# iPlayer.net
KiCad netlist of a schematic drawn in EasyEDA Pro
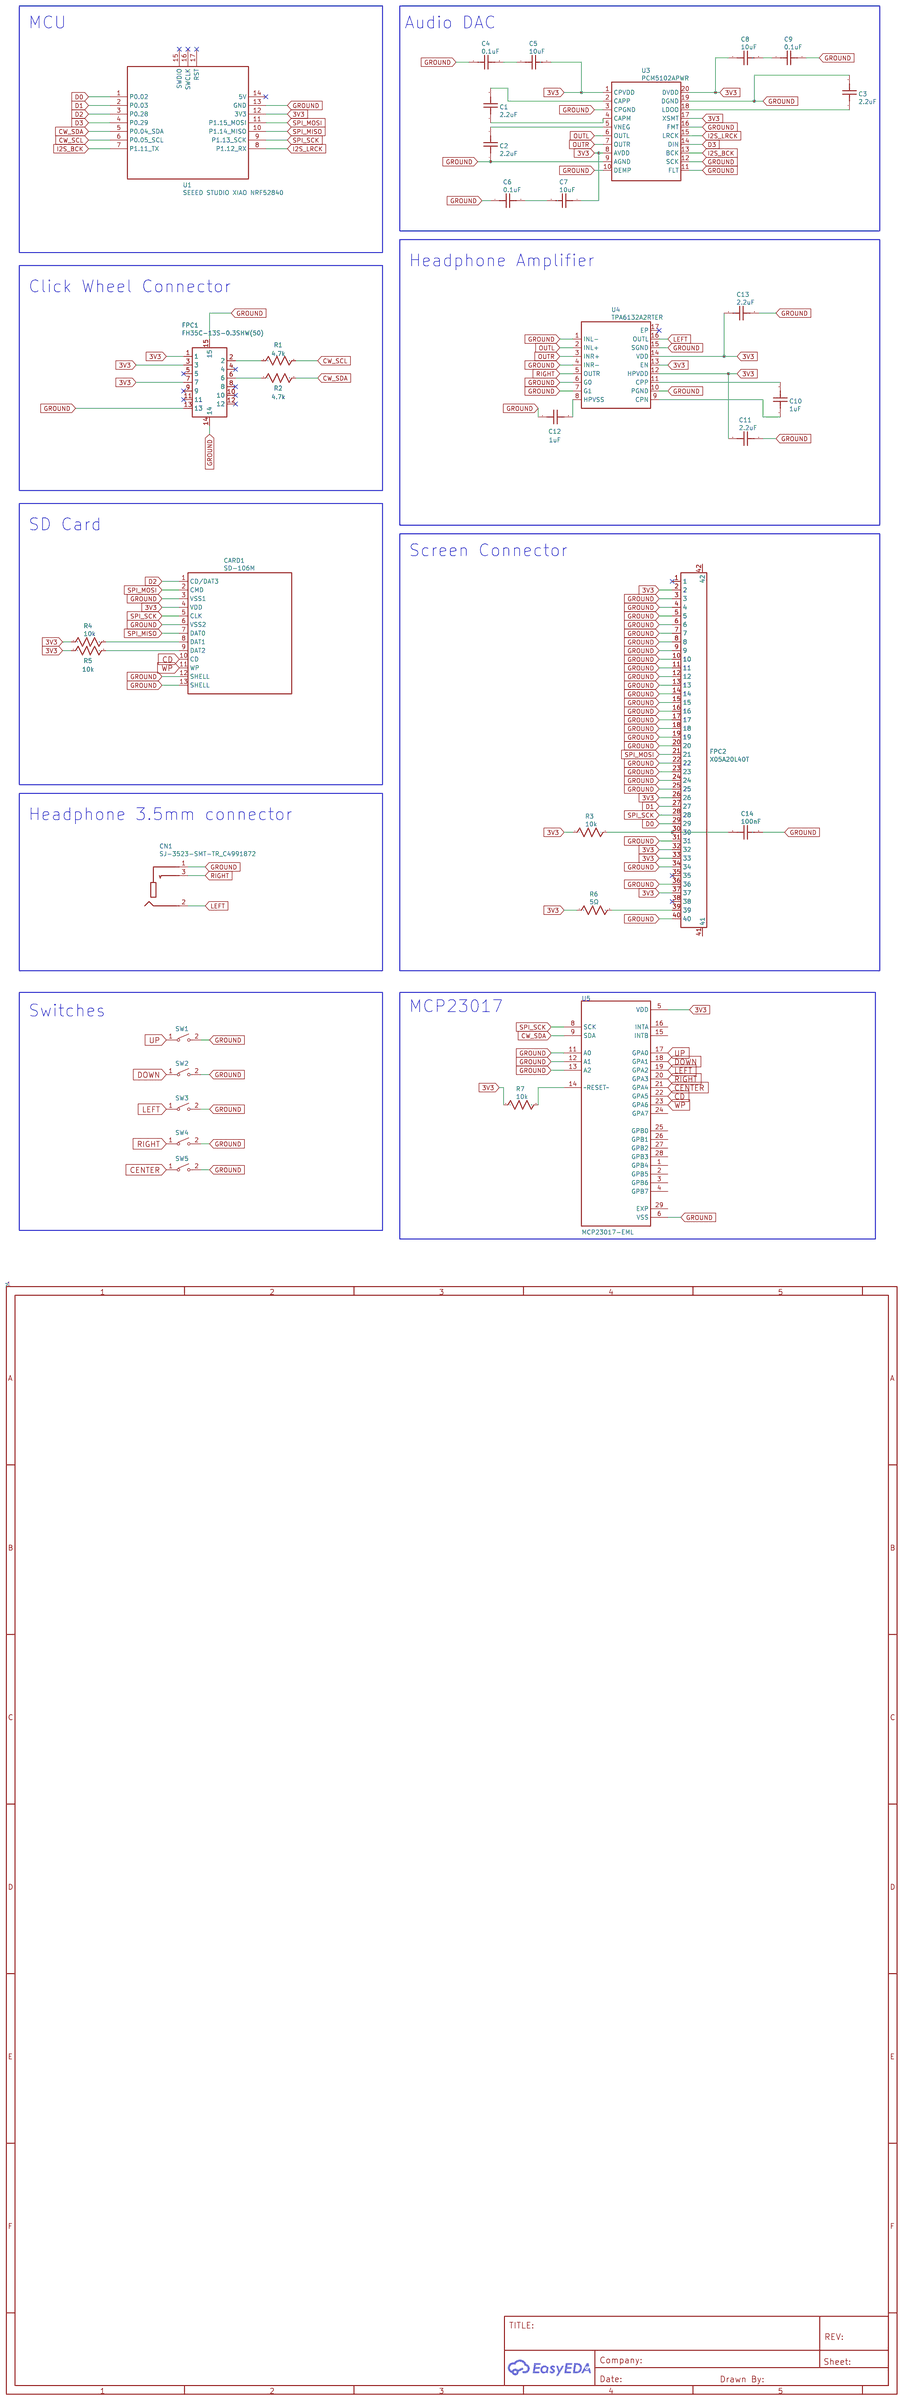
[diagram p0: schematic sheet]

(export (version "E")
  (design (tool "Eeschema 10.0.6"))
  (components
    (comp (ref "C1")
      (value "2.2uF")
      (footprint "easyedapro:C0603")
      (fields (field (name "Contributor") "LCEDA_Lib"))
      (libsource (lib "easyedapro") (part "2.2uF"))
    )
    (comp (ref "C2")
      (value "2.2uF")
      (footprint "easyedapro:C0603")
      (fields (field (name "Contributor") "LCEDA_Lib"))
      (libsource (lib "easyedapro") (part "2.2uF"))
    )
    (comp (ref "C3")
      (value "2.2uF")
      (footprint "easyedapro:C0603")
      (fields (field (name "Contributor") "LCEDA_Lib"))
      (libsource (lib "easyedapro") (part "2.2uF"))
    )
    (comp (ref "C4")
      (value "0.1uF")
      (footprint "easyedapro:C0603")
      (fields (field (name "Contributor") "LCEDA_Lib"))
      (libsource (lib "easyedapro") (part "0.1uF"))
    )
    (comp (ref "C5")
      (value "10uF")
      (footprint "easyedapro:C0603")
      (fields (field (name "Contributor") "LCEDA_Lib"))
      (libsource (lib "easyedapro") (part "10uF"))
    )
    (comp (ref "C6")
      (value "0.1uF")
      (footprint "easyedapro:C0603")
      (fields (field (name "Contributor") "LCEDA_Lib"))
      (libsource (lib "easyedapro") (part "0.1uF"))
    )
    (comp (ref "C7")
      (value "10uF")
      (footprint "easyedapro:C0603")
      (fields (field (name "Contributor") "LCEDA_Lib"))
      (libsource (lib "easyedapro") (part "10uF"))
    )
    (comp (ref "C8")
      (value "10uF")
      (footprint "easyedapro:C0603")
      (fields (field (name "Contributor") "LCEDA_Lib"))
      (libsource (lib "easyedapro") (part "10uF"))
    )
    (comp (ref "C9")
      (value "0.1uF")
      (footprint "easyedapro:C0603")
      (fields (field (name "Contributor") "LCEDA_Lib"))
      (libsource (lib "easyedapro") (part "0.1uF"))
    )
    (comp (ref "C10")
      (value "1uF")
      (footprint "easyedapro:C0603")
      (fields (field (name "Contributor") "LCEDA_Lib"))
      (libsource (lib "easyedapro") (part "1uF"))
    )
    (comp (ref "C11")
      (value "2.2uF")
      (footprint "easyedapro:C0603")
      (fields (field (name "Contributor") "LCEDA_Lib"))
      (libsource (lib "easyedapro") (part "2.2uF"))
    )
    (comp (ref "C12")
      (value "1uF")
      (footprint "easyedapro:C0603")
      (fields (field (name "Contributor") "LCEDA_Lib"))
      (libsource (lib "easyedapro") (part "1uF"))
    )
    (comp (ref "C13")
      (value "2.2uF")
      (footprint "easyedapro:C0603")
      (fields (field (name "Contributor") "LCEDA_Lib"))
      (libsource (lib "easyedapro") (part "2.2uF"))
    )
    (comp (ref "C14")
      (value "100nF")
      (footprint "easyedapro:C0603")
      (fields (field (name "Contributor") "LCEDA_Lib"))
      (libsource (lib "easyedapro") (part "100nF"))
    )
    (comp (ref "CARD1")
      (value "SD-106M")
      (footprint "easyedapro:SD-SMD_SD-106M")
      (fields (field (name "Manufacturer") "XUNPU(讯普)") (field (name "Contributor") "LCSC"))
      (libsource (lib "easyedapro") (part "SD-106M"))
    )
    (comp (ref "CN1")
      (value "SJ-3523-SMT-TR_C4991872")
      (footprint "easyedapro:AUDIO-SMD_SJ-3523-SMT-TR")
      (fields
        (field (name "Manufacturer Part") "SJ-3523-SMT-TR")
        (field (name "Manufacturer") "CUI")
        (field (name "Contributor") "lcsc")
      )
      (libsource (lib "easyedapro") (part "SJ-3523-SMT-TR_C4991872"))
    )
    (comp (ref "FPC1")
      (value "FH35C-13S-0.3SHW(50)")
      (footprint "easyedapro:FPC-SMD_13P-P0.60_HRS_FH35C-13S-0.3SHW")
      (fields (field (name "Manufacturer") "HRS(广濑)") (field (name "Contributor") "LCSC"))
      (libsource (lib "easyedapro") (part "FH35C-13S-0.3SHW(50)"))
    )
    (comp (ref "FPC2")
      (value "X05A20L40T")
      (footprint "easyedapro:FFC-SMD_40P-P0.50_X05A20L40T")
      (fields (field (name "Manufacturer") "XKB Connection(中国星坤)") (field (name "Contributor") "LCSC"))
      (libsource (lib "easyedapro") (part "X05A20L40T"))
    )
    (comp (ref "R1")
      (value "4.7k")
      (footprint "easyedapro:R0603")
      (fields (field (name "Contributor") "LCEDA_Lib"))
      (libsource (lib "easyedapro") (part "4.7k"))
    )
    (comp (ref "R2")
      (value "4.7k")
      (footprint "easyedapro:R0603")
      (fields (field (name "Contributor") "LCEDA_Lib"))
      (libsource (lib "easyedapro") (part "4.7k"))
    )
    (comp (ref "R3")
      (value "10k")
      (footprint "easyedapro:R0603")
      (fields (field (name "Contributor") "LCEDA_Lib"))
      (libsource (lib "easyedapro") (part "10k"))
    )
    (comp (ref "R4")
      (value "10k")
      (footprint "easyedapro:R0603")
      (fields (field (name "Contributor") "LCEDA_Lib"))
      (libsource (lib "easyedapro") (part "10k"))
    )
    (comp (ref "R5")
      (value "10k")
      (footprint "easyedapro:R0603")
      (fields (field (name "Contributor") "LCEDA_Lib"))
      (libsource (lib "easyedapro") (part "10k"))
    )
    (comp (ref "R6")
      (value "5Ω")
      (footprint "easyedapro:R0603")
      (fields (field (name "Contributor") "LCEDA_Lib"))
      (libsource (lib "easyedapro") (part "5Ω"))
    )
    (comp (ref "R7")
      (value "10k")
      (footprint "easyedapro:R0603")
      (fields (field (name "Contributor") "LCEDA_Lib"))
      (libsource (lib "easyedapro") (part "10k"))
    )
    (comp (ref "SW1")
      (value "~")
      (footprint "easyedapro:SW-SMD_L3.9-W3.0-P4.45")
      (fields (field (name "Manufacturer Part") "TS-1088R-02026") (field (name "Manufacturer") "XUNPU(讯普)"))
      (libsource (lib "easyedapro") (part "TS-1088R-02026"))
    )
    (comp (ref "SW2")
      (value "~")
      (footprint "easyedapro:SW-SMD_L3.9-W3.0-P4.45")
      (fields (field (name "Manufacturer Part") "TS-1088R-02026") (field (name "Manufacturer") "XUNPU(讯普)"))
      (libsource (lib "easyedapro") (part "TS-1088R-02026"))
    )
    (comp (ref "SW3")
      (value "~")
      (footprint "easyedapro:SW-SMD_L3.9-W3.0-P4.45")
      (fields (field (name "Manufacturer Part") "TS-1088R-02026") (field (name "Manufacturer") "XUNPU(讯普)"))
      (libsource (lib "easyedapro") (part "TS-1088R-02026"))
    )
    (comp (ref "SW4")
      (value "~")
      (footprint "easyedapro:SW-SMD_L3.9-W3.0-P4.45")
      (fields (field (name "Manufacturer Part") "TS-1088R-02026") (field (name "Manufacturer") "XUNPU(讯普)"))
      (libsource (lib "easyedapro") (part "TS-1088R-02026"))
    )
    (comp (ref "SW5")
      (value "~")
      (footprint "easyedapro:SW-SMD_L3.9-W3.0-P4.45")
      (fields (field (name "Manufacturer Part") "TS-1088R-02026") (field (name "Manufacturer") "XUNPU(讯普)"))
      (libsource (lib "easyedapro") (part "TS-1088R-02026"))
    )
    (comp (ref "U1")
      (value "SEEED STUDIO XIAO NRF52840")
      (footprint "easyedapro:SEEED STUDIO XIAO NRF52840")
      (fields (field (name "Contributor") "hafeneger"))
      (libsource (lib "easyedapro") (part "SEEED STUDIO XIAO NRF52840"))
    )
    (comp (ref "U3")
      (value "PCM5102APWR")
      (footprint "easyedapro:TSSOP-20_L6.5-W4.4-P0.65-LS6.4-BL")
      (fields (field (name "Manufacturer") "TI(德州仪器)") (field (name "Contributor") "LCSC"))
      (libsource (lib "easyedapro") (part "PCM5102APWR"))
    )
    (comp (ref "U4")
      (value "TPA6132A2RTER")
      (footprint "easyedapro:WQFN-16_L3.0-W3.0-P0.50-TL-EP1.6")
      (fields (field (name "Manufacturer") "TI(德州仪器)"))
      (libsource (lib "easyedapro") (part "TPA6132A2RTER"))
    )
    (comp (ref "U5")
      (value "MCP23017-EML")
      (footprint "easyedapro:QFN65P600X600X100-29N")
      (libsource (lib "easyedapro") (part "MCP23017-EML"))
    )
  )
  (nets
    (net (code "1") (name "3V3") (class "Default")
      (node (ref "C11") (pin "2") (pinfunction "2_2") (pintype "unspecified"))
      (node (ref "C13") (pin "1") (pinfunction "1_1") (pintype "unspecified"))
      (node (ref "C5") (pin "2") (pinfunction "2_2") (pintype "unspecified"))
      (node (ref "C7") (pin "1") (pinfunction "1_1") (pintype "unspecified"))
      (node (ref "C8") (pin "1") (pinfunction "1_1") (pintype "unspecified"))
      (node (ref "CARD1") (pin "4") (pinfunction "VDD_4") (pintype "unspecified"))
      (node (ref "FPC1") (pin "1") (pinfunction "1_1") (pintype "unspecified"))
      (node (ref "FPC1") (pin "3") (pinfunction "3_3") (pintype "unspecified"))
      (node (ref "FPC1") (pin "7") (pinfunction "7_7") (pintype "unspecified"))
      (node (ref "FPC2") (pin "2") (pinfunction "2_2") (pintype "unspecified"))
      (node (ref "FPC2") (pin "26") (pinfunction "26_26") (pintype "unspecified"))
      (node (ref "FPC2") (pin "32") (pinfunction "32_32") (pintype "unspecified"))
      (node (ref "FPC2") (pin "33") (pinfunction "33_33") (pintype "unspecified"))
      (node (ref "FPC2") (pin "37") (pinfunction "37_37") (pintype "unspecified"))
      (node (ref "R3") (pin "1") (pinfunction "1_1") (pintype "unspecified"))
      (node (ref "R4") (pin "1") (pinfunction "1_1") (pintype "unspecified"))
      (node (ref "R5") (pin "1") (pinfunction "1_1") (pintype "unspecified"))
      (node (ref "R6") (pin "1") (pinfunction "1_1") (pintype "unspecified"))
      (node (ref "R7") (pin "1") (pinfunction "1_1") (pintype "unspecified"))
      (node (ref "U1") (pin "12") (pinfunction "3V3_12") (pintype "unspecified"))
      (node (ref "U3") (pin "1") (pinfunction "CPVDD_1") (pintype "unspecified"))
      (node (ref "U3") (pin "17") (pinfunction "XSMT_17") (pintype "unspecified"))
      (node (ref "U3") (pin "20") (pinfunction "DVDD_20") (pintype "unspecified"))
      (node (ref "U3") (pin "8") (pinfunction "AVDD_8") (pintype "unspecified"))
      (node (ref "U4") (pin "12") (pinfunction "HPVDD_12") (pintype "unspecified"))
      (node (ref "U4") (pin "13") (pinfunction "EN_13") (pintype "unspecified"))
      (node (ref "U4") (pin "14") (pinfunction "VDD_14") (pintype "unspecified"))
      (node (ref "U5") (pin "5") (pinfunction "VDD_5") (pintype "unspecified"))
    )
    (net (code "2") (name "CD") (class "Default")
      (node (ref "CARD1") (pin "10") (pinfunction "CD_10") (pintype "unspecified"))
      (node (ref "U5") (pin "22") (pinfunction "GPA5_22") (pintype "bidirectional"))
    )
    (net (code "3") (name "CENTER") (class "Default")
      (node (ref "SW5") (pin "1") (pinfunction "1_1") (pintype "input"))
      (node (ref "U5") (pin "21") (pinfunction "GPA4_21") (pintype "bidirectional"))
    )
    (net (code "4") (name "CW_SCL") (class "Default")
      (node (ref "R1") (pin "2") (pinfunction "2_2") (pintype "unspecified"))
      (node (ref "U1") (pin "6") (pinfunction "P0.05_SCL_6") (pintype "unspecified"))
    )
    (net (code "5") (name "CW_SDA") (class "Default")
      (node (ref "R2") (pin "2") (pinfunction "2_2") (pintype "unspecified"))
      (node (ref "U1") (pin "5") (pinfunction "P0.04_SDA_5") (pintype "unspecified"))
      (node (ref "U5") (pin "9") (pinfunction "SDA_9") (pintype "bidirectional"))
    )
    (net (code "6") (name "D0") (class "Default")
      (node (ref "FPC2") (pin "29") (pinfunction "29_29") (pintype "unspecified"))
      (node (ref "U1") (pin "1") (pinfunction "P0.02_1") (pintype "input"))
    )
    (net (code "7") (name "D1") (class "Default")
      (node (ref "FPC2") (pin "27") (pinfunction "27_27") (pintype "unspecified"))
      (node (ref "U1") (pin "2") (pinfunction "P0.03_2") (pintype "output"))
    )
    (net (code "8") (name "D2") (class "Default")
      (node (ref "CARD1") (pin "1") (pinfunction "CD/DAT3_1") (pintype "unspecified"))
      (node (ref "U1") (pin "3") (pinfunction "P0.28_3") (pintype "bidirectional"))
    )
    (net (code "9") (name "D3") (class "Default")
      (node (ref "U1") (pin "4") (pinfunction "P0.29_4") (pintype "unspecified"))
      (node (ref "U3") (pin "14") (pinfunction "DIN_14") (pintype "unspecified"))
    )
    (net (code "10") (name "DOWN") (class "Default")
      (node (ref "SW2") (pin "1") (pinfunction "1_1") (pintype "input"))
      (node (ref "U5") (pin "18") (pinfunction "GPA1_18") (pintype "bidirectional"))
    )
    (net (code "11") (name "GROUND") (class "Default")
      (node (ref "C11") (pin "1") (pinfunction "1_1") (pintype "unspecified"))
      (node (ref "C12") (pin "1") (pinfunction "1_1") (pintype "unspecified"))
      (node (ref "C13") (pin "2") (pinfunction "2_2") (pintype "unspecified"))
      (node (ref "C14") (pin "2") (pinfunction "2_2") (pintype "unspecified"))
      (node (ref "C2") (pin "1") (pinfunction "1_1") (pintype "unspecified"))
      (node (ref "C3") (pin "2") (pinfunction "2_2") (pintype "unspecified"))
      (node (ref "C4") (pin "1") (pinfunction "1_1") (pintype "unspecified"))
      (node (ref "C6") (pin "1") (pinfunction "1_1") (pintype "unspecified"))
      (node (ref "C9") (pin "2") (pinfunction "2_2") (pintype "unspecified"))
      (node (ref "CARD1") (pin "12") (pinfunction "SHELL_12") (pintype "unspecified"))
      (node (ref "CARD1") (pin "13") (pinfunction "SHELL_13") (pintype "unspecified"))
      (node (ref "CARD1") (pin "3") (pinfunction "VSS1_3") (pintype "unspecified"))
      (node (ref "CARD1") (pin "6") (pinfunction "VSS2_6") (pintype "unspecified"))
      (node (ref "CN1") (pin "1") (pinfunction "1_1") (pintype "unspecified"))
      (node (ref "FPC1") (pin "13") (pinfunction "13_13") (pintype "unspecified"))
      (node (ref "FPC1") (pin "14") (pinfunction "14_14") (pintype "unspecified"))
      (node (ref "FPC1") (pin "15") (pinfunction "15_15") (pintype "unspecified"))
      (node (ref "FPC2") (pin "10") (pinfunction "10_10") (pintype "unspecified"))
      (node (ref "FPC2") (pin "11") (pinfunction "11_11") (pintype "unspecified"))
      (node (ref "FPC2") (pin "12") (pinfunction "12_12") (pintype "unspecified"))
      (node (ref "FPC2") (pin "13") (pinfunction "13_13") (pintype "unspecified"))
      (node (ref "FPC2") (pin "14") (pinfunction "14_14") (pintype "unspecified"))
      (node (ref "FPC2") (pin "15") (pinfunction "15_15") (pintype "unspecified"))
      (node (ref "FPC2") (pin "16") (pinfunction "16_16") (pintype "unspecified"))
      (node (ref "FPC2") (pin "17") (pinfunction "17_17") (pintype "unspecified"))
      (node (ref "FPC2") (pin "18") (pinfunction "18_18") (pintype "unspecified"))
      (node (ref "FPC2") (pin "19") (pinfunction "19_19") (pintype "unspecified"))
      (node (ref "FPC2") (pin "20") (pinfunction "20_20") (pintype "unspecified"))
      (node (ref "FPC2") (pin "22") (pinfunction "22_22") (pintype "unspecified"))
      (node (ref "FPC2") (pin "23") (pinfunction "23_23") (pintype "unspecified"))
      (node (ref "FPC2") (pin "24") (pinfunction "24_24") (pintype "unspecified"))
      (node (ref "FPC2") (pin "25") (pinfunction "25_25") (pintype "unspecified"))
      (node (ref "FPC2") (pin "3") (pinfunction "3_3") (pintype "unspecified"))
      (node (ref "FPC2") (pin "31") (pinfunction "31_31") (pintype "unspecified"))
      (node (ref "FPC2") (pin "34") (pinfunction "34_34") (pintype "unspecified"))
      (node (ref "FPC2") (pin "36") (pinfunction "36_36") (pintype "unspecified"))
      (node (ref "FPC2") (pin "4") (pinfunction "4_4") (pintype "unspecified"))
      (node (ref "FPC2") (pin "40") (pinfunction "40_40") (pintype "unspecified"))
      (node (ref "FPC2") (pin "5") (pinfunction "5_5") (pintype "unspecified"))
      (node (ref "FPC2") (pin "6") (pinfunction "6_6") (pintype "unspecified"))
      (node (ref "FPC2") (pin "7") (pinfunction "7_7") (pintype "unspecified"))
      (node (ref "FPC2") (pin "8") (pinfunction "8_8") (pintype "unspecified"))
      (node (ref "FPC2") (pin "9") (pinfunction "9_9") (pintype "unspecified"))
      (node (ref "SW1") (pin "2") (pinfunction "2_2") (pintype "input"))
      (node (ref "SW2") (pin "2") (pinfunction "2_2") (pintype "input"))
      (node (ref "SW3") (pin "2") (pinfunction "2_2") (pintype "input"))
      (node (ref "SW4") (pin "2") (pinfunction "2_2") (pintype "input"))
      (node (ref "SW5") (pin "2") (pinfunction "2_2") (pintype "input"))
      (node (ref "U1") (pin "13") (pinfunction "GND_13") (pintype "unspecified"))
      (node (ref "U3") (pin "10") (pinfunction "DEMP_10") (pintype "unspecified"))
      (node (ref "U3") (pin "11") (pinfunction "FLT_11") (pintype "unspecified"))
      (node (ref "U3") (pin "12") (pinfunction "SCK_12") (pintype "unspecified"))
      (node (ref "U3") (pin "16") (pinfunction "FMT_16") (pintype "unspecified"))
      (node (ref "U3") (pin "19") (pinfunction "DGND_19") (pintype "unspecified"))
      (node (ref "U3") (pin "3") (pinfunction "CPGND_3") (pintype "unspecified"))
      (node (ref "U3") (pin "9") (pinfunction "AGND_9") (pintype "unspecified"))
      (node (ref "U4") (pin "1") (pinfunction "INL-_1") (pintype "unspecified"))
      (node (ref "U4") (pin "10") (pinfunction "PGND_10") (pintype "unspecified"))
      (node (ref "U4") (pin "15") (pinfunction "SGND_15") (pintype "unspecified"))
      (node (ref "U4") (pin "4") (pinfunction "INR-_4") (pintype "unspecified"))
      (node (ref "U4") (pin "6") (pinfunction "G0_6") (pintype "unspecified"))
      (node (ref "U4") (pin "7") (pinfunction "G1_7") (pintype "unspecified"))
      (node (ref "U5") (pin "11") (pinfunction "A0_11") (pintype "input"))
      (node (ref "U5") (pin "12") (pinfunction "A1_12") (pintype "input"))
      (node (ref "U5") (pin "13") (pinfunction "A2_13") (pintype "input"))
      (node (ref "U5") (pin "6") (pinfunction "VSS_6") (pintype "unspecified"))
    )
    (net (code "12") (name "I2S_BCK") (class "Default")
      (node (ref "U1") (pin "7") (pinfunction "P1.11_TX_7") (pintype "unspecified"))
      (node (ref "U3") (pin "13") (pinfunction "BCK_13") (pintype "unspecified"))
    )
    (net (code "13") (name "I2S_LRCK") (class "Default")
      (node (ref "U1") (pin "8") (pinfunction "P1.12_RX_8") (pintype "unspecified"))
      (node (ref "U3") (pin "15") (pinfunction "LRCK_15") (pintype "unspecified"))
    )
    (net (code "14") (name "LEFT") (class "Default")
      (node (ref "CN1") (pin "2") (pinfunction "2_2") (pintype "unspecified"))
      (node (ref "SW3") (pin "1") (pinfunction "1_1") (pintype "input"))
      (node (ref "U4") (pin "16") (pinfunction "OUTL_16") (pintype "unspecified"))
      (node (ref "U5") (pin "19") (pinfunction "GPA2_19") (pintype "bidirectional"))
    )
    (net (code "15") (name "Net-(C4-Pad2)") (class "Default")
      (node (ref "C4") (pin "2") (pinfunction "2_2") (pintype "unspecified"))
      (node (ref "C5") (pin "1") (pinfunction "1_1") (pintype "unspecified"))
    )
    (net (code "16") (name "Net-(C6-Pad2)") (class "Default")
      (node (ref "C6") (pin "2") (pinfunction "2_2") (pintype "unspecified"))
      (node (ref "C7") (pin "2") (pinfunction "2_2") (pintype "unspecified"))
    )
    (net (code "17") (name "Net-(C8-Pad2)") (class "Default")
      (node (ref "C8") (pin "2") (pinfunction "2_2") (pintype "unspecified"))
      (node (ref "C9") (pin "1") (pinfunction "1_1") (pintype "unspecified"))
    )
    (net (code "18") (name "Net-(C14-Pad1)") (class "Default")
      (node (ref "C14") (pin "1") (pinfunction "1_1") (pintype "unspecified"))
      (node (ref "FPC2") (pin "30") (pinfunction "30_30") (pintype "unspecified"))
      (node (ref "R3") (pin "2") (pinfunction "2_2") (pintype "unspecified"))
    )
    (net (code "19") (name "Net-(CARD1-DAT1)") (class "Default")
      (node (ref "CARD1") (pin "8") (pinfunction "DAT1_8") (pintype "unspecified"))
      (node (ref "R4") (pin "2") (pinfunction "2_2") (pintype "unspecified"))
    )
    (net (code "20") (name "Net-(CARD1-DAT2)") (class "Default")
      (node (ref "CARD1") (pin "9") (pinfunction "DAT2_9") (pintype "unspecified"))
      (node (ref "R5") (pin "2") (pinfunction "2_2") (pintype "unspecified"))
    )
    (net (code "21") (name "Net-(FPC1-Pad2)") (class "Default")
      (node (ref "FPC1") (pin "2") (pinfunction "2_2") (pintype "unspecified"))
      (node (ref "R1") (pin "1") (pinfunction "1_1") (pintype "unspecified"))
    )
    (net (code "22") (name "Net-(FPC1-Pad6)") (class "Default")
      (node (ref "FPC1") (pin "6") (pinfunction "6_6") (pintype "unspecified"))
      (node (ref "R2") (pin "1") (pinfunction "1_1") (pintype "unspecified"))
    )
    (net (code "23") (name "Net-(FPC2-Pad39)") (class "Default")
      (node (ref "FPC2") (pin "39") (pinfunction "39_39") (pintype "unspecified"))
      (node (ref "R6") (pin "2") (pinfunction "2_2") (pintype "unspecified"))
    )
    (net (code "24") (name "Net-(U3-CAPM)") (class "Default")
      (node (ref "C1") (pin "1") (pinfunction "1_1") (pintype "unspecified"))
      (node (ref "U3") (pin "4") (pinfunction "CAPM_4") (pintype "unspecified"))
    )
    (net (code "25") (name "Net-(U3-CAPP)") (class "Default")
      (node (ref "C1") (pin "2") (pinfunction "2_2") (pintype "unspecified"))
      (node (ref "U3") (pin "2") (pinfunction "CAPP_2") (pintype "unspecified"))
    )
    (net (code "26") (name "Net-(U3-LDOO)") (class "Default")
      (node (ref "C3") (pin "1") (pinfunction "1_1") (pintype "unspecified"))
      (node (ref "U3") (pin "18") (pinfunction "LDOO_18") (pintype "unspecified"))
    )
    (net (code "27") (name "Net-(U3-VNEG)") (class "Default")
      (node (ref "C2") (pin "2") (pinfunction "2_2") (pintype "unspecified"))
      (node (ref "U3") (pin "5") (pinfunction "VNEG_5") (pintype "unspecified"))
    )
    (net (code "28") (name "Net-(U4-CPN)") (class "Default")
      (node (ref "C10") (pin "1") (pinfunction "1_1") (pintype "unspecified"))
      (node (ref "U4") (pin "9") (pinfunction "CPN_9") (pintype "unspecified"))
    )
    (net (code "29") (name "Net-(U4-CPP)") (class "Default")
      (node (ref "C10") (pin "2") (pinfunction "2_2") (pintype "unspecified"))
      (node (ref "U4") (pin "11") (pinfunction "CPP_11") (pintype "unspecified"))
    )
    (net (code "30") (name "Net-(U4-HPVSS)") (class "Default")
      (node (ref "C12") (pin "2") (pinfunction "2_2") (pintype "unspecified"))
      (node (ref "U4") (pin "8") (pinfunction "HPVSS_8") (pintype "unspecified"))
    )
    (net (code "31") (name "Net-(U5-~RESET~)") (class "Default")
      (node (ref "R7") (pin "2") (pinfunction "2_2") (pintype "unspecified"))
      (node (ref "U5") (pin "14") (pinfunction "~RESET~_14") (pintype "input"))
    )
    (net (code "32") (name "OUTL") (class "Default")
      (node (ref "U3") (pin "6") (pinfunction "OUTL_6") (pintype "unspecified"))
      (node (ref "U4") (pin "2") (pinfunction "INL+_2") (pintype "unspecified"))
    )
    (net (code "33") (name "OUTR") (class "Default")
      (node (ref "U3") (pin "7") (pinfunction "OUTR_7") (pintype "unspecified"))
      (node (ref "U4") (pin "3") (pinfunction "INR+_3") (pintype "unspecified"))
    )
    (net (code "34") (name "RIGHT") (class "Default")
      (node (ref "CN1") (pin "3") (pinfunction "3_3") (pintype "unspecified"))
      (node (ref "SW4") (pin "1") (pinfunction "1_1") (pintype "input"))
      (node (ref "U4") (pin "5") (pinfunction "OUTR_5") (pintype "unspecified"))
      (node (ref "U5") (pin "20") (pinfunction "GPA3_20") (pintype "bidirectional"))
    )
    (net (code "35") (name "SPI_MISO") (class "Default")
      (node (ref "CARD1") (pin "7") (pinfunction "DAT0_7") (pintype "unspecified"))
      (node (ref "U1") (pin "10") (pinfunction "P1.14_MISO_10") (pintype "unspecified"))
    )
    (net (code "36") (name "SPI_MOSI") (class "Default")
      (node (ref "CARD1") (pin "2") (pinfunction "CMD_2") (pintype "unspecified"))
      (node (ref "FPC2") (pin "21") (pinfunction "21_21") (pintype "unspecified"))
      (node (ref "U1") (pin "11") (pinfunction "P1.15_MOSI_11") (pintype "unspecified"))
    )
    (net (code "37") (name "SPI_SCK") (class "Default")
      (node (ref "CARD1") (pin "5") (pinfunction "CLK_5") (pintype "unspecified"))
      (node (ref "FPC2") (pin "28") (pinfunction "28_28") (pintype "unspecified"))
      (node (ref "U1") (pin "9") (pinfunction "P1.13_SCK_9") (pintype "unspecified"))
      (node (ref "U5") (pin "8") (pinfunction "SCK_8") (pintype "input"))
    )
    (net (code "38") (name "UP") (class "Default")
      (node (ref "SW1") (pin "1") (pinfunction "1_1") (pintype "input"))
      (node (ref "U5") (pin "17") (pinfunction "GPA0_17") (pintype "bidirectional"))
    )
    (net (code "39") (name "WP") (class "Default")
      (node (ref "CARD1") (pin "11") (pinfunction "WP_11") (pintype "unspecified"))
      (node (ref "U5") (pin "23") (pinfunction "GPA6_23") (pintype "bidirectional"))
    )
    (net (code "40") (name "unconnected-(FPC1-Pad4)") (class "Default")
      (node (ref "FPC1") (pin "4") (pinfunction "4_4") (pintype "unspecified+no_connect"))
    )
    (net (code "41") (name "unconnected-(FPC1-Pad5)") (class "Default")
      (node (ref "FPC1") (pin "5") (pinfunction "5_5") (pintype "unspecified+no_connect"))
    )
    (net (code "42") (name "unconnected-(FPC1-Pad8)") (class "Default")
      (node (ref "FPC1") (pin "8") (pinfunction "8_8") (pintype "unspecified+no_connect"))
    )
    (net (code "43") (name "unconnected-(FPC1-Pad9)") (class "Default")
      (node (ref "FPC1") (pin "9") (pinfunction "9_9") (pintype "unspecified+no_connect"))
    )
    (net (code "44") (name "unconnected-(FPC1-Pad10)") (class "Default")
      (node (ref "FPC1") (pin "10") (pinfunction "10_10") (pintype "unspecified+no_connect"))
    )
    (net (code "45") (name "unconnected-(FPC1-Pad11)") (class "Default")
      (node (ref "FPC1") (pin "11") (pinfunction "11_11") (pintype "unspecified+no_connect"))
    )
    (net (code "46") (name "unconnected-(FPC1-Pad12)") (class "Default")
      (node (ref "FPC1") (pin "12") (pinfunction "12_12") (pintype "unspecified+no_connect"))
    )
    (net (code "47") (name "unconnected-(FPC2-Pad1)") (class "Default")
      (node (ref "FPC2") (pin "1") (pinfunction "1_1") (pintype "unspecified+no_connect"))
    )
    (net (code "48") (name "unconnected-(FPC2-Pad35)") (class "Default")
      (node (ref "FPC2") (pin "35") (pinfunction "35_35") (pintype "unspecified+no_connect"))
    )
    (net (code "49") (name "unconnected-(FPC2-Pad38)") (class "Default")
      (node (ref "FPC2") (pin "38") (pinfunction "38_38") (pintype "unspecified+no_connect"))
    )
    (net (code "50") (name "unconnected-(FPC2-Pad41)") (class "Default")
      (node (ref "FPC2") (pin "41") (pinfunction "41_41") (pintype "unspecified"))
    )
    (net (code "51") (name "unconnected-(FPC2-Pad42)") (class "Default")
      (node (ref "FPC2") (pin "42") (pinfunction "42_42") (pintype "unspecified"))
    )
    (net (code "52") (name "unconnected-(U1-5V-Pad14)") (class "Default")
      (node (ref "U1") (pin "14") (pinfunction "5V_14") (pintype "unspecified+no_connect"))
    )
    (net (code "53") (name "unconnected-(U1-RST-Pad17)") (class "Default")
      (node (ref "U1") (pin "17") (pinfunction "RST_17") (pintype "unspecified+no_connect"))
    )
    (net (code "54") (name "unconnected-(U1-SWCLK-Pad16)") (class "Default")
      (node (ref "U1") (pin "16") (pinfunction "SWCLK_16") (pintype "unspecified+no_connect"))
    )
    (net (code "55") (name "unconnected-(U1-SWDIO-Pad15)") (class "Default")
      (node (ref "U1") (pin "15") (pinfunction "SWDIO_15") (pintype "unspecified+no_connect"))
    )
    (net (code "56") (name "unconnected-(U4-EP-Pad17)") (class "Default")
      (node (ref "U4") (pin "17") (pinfunction "EP_17") (pintype "unspecified+no_connect"))
    )
    (net (code "57") (name "unconnected-(U5-EXP-Pad29)") (class "Default")
      (node (ref "U5") (pin "29") (pinfunction "EXP_29") (pintype "unspecified"))
    )
    (net (code "58") (name "unconnected-(U5-GPA7-Pad24)") (class "Default")
      (node (ref "U5") (pin "24") (pinfunction "GPA7_24") (pintype "bidirectional"))
    )
    (net (code "59") (name "unconnected-(U5-GPB0-Pad25)") (class "Default")
      (node (ref "U5") (pin "25") (pinfunction "GPB0_25") (pintype "bidirectional"))
    )
    (net (code "60") (name "unconnected-(U5-GPB1-Pad26)") (class "Default")
      (node (ref "U5") (pin "26") (pinfunction "GPB1_26") (pintype "bidirectional"))
    )
    (net (code "61") (name "unconnected-(U5-GPB2-Pad27)") (class "Default")
      (node (ref "U5") (pin "27") (pinfunction "GPB2_27") (pintype "bidirectional"))
    )
    (net (code "62") (name "unconnected-(U5-GPB3-Pad28)") (class "Default")
      (node (ref "U5") (pin "28") (pinfunction "GPB3_28") (pintype "bidirectional"))
    )
    (net (code "63") (name "unconnected-(U5-GPB4-Pad1)") (class "Default")
      (node (ref "U5") (pin "1") (pinfunction "GPB4_1") (pintype "bidirectional"))
    )
    (net (code "64") (name "unconnected-(U5-GPB5-Pad2)") (class "Default")
      (node (ref "U5") (pin "2") (pinfunction "GPB5_2") (pintype "bidirectional"))
    )
    (net (code "65") (name "unconnected-(U5-GPB6-Pad3)") (class "Default")
      (node (ref "U5") (pin "3") (pinfunction "GPB6_3") (pintype "bidirectional"))
    )
    (net (code "66") (name "unconnected-(U5-GPB7-Pad4)") (class "Default")
      (node (ref "U5") (pin "4") (pinfunction "GPB7_4") (pintype "bidirectional"))
    )
    (net (code "67") (name "unconnected-(U5-INTA-Pad16)") (class "Default")
      (node (ref "U5") (pin "16") (pinfunction "INTA_16") (pintype "output"))
    )
    (net (code "68") (name "unconnected-(U5-INTB-Pad15)") (class "Default")
      (node (ref "U5") (pin "15") (pinfunction "INTB_15") (pintype "output"))
    )
  )
)
